# bigSevenV3.net
KiCad netlist of a schematic drawn in EAGLE
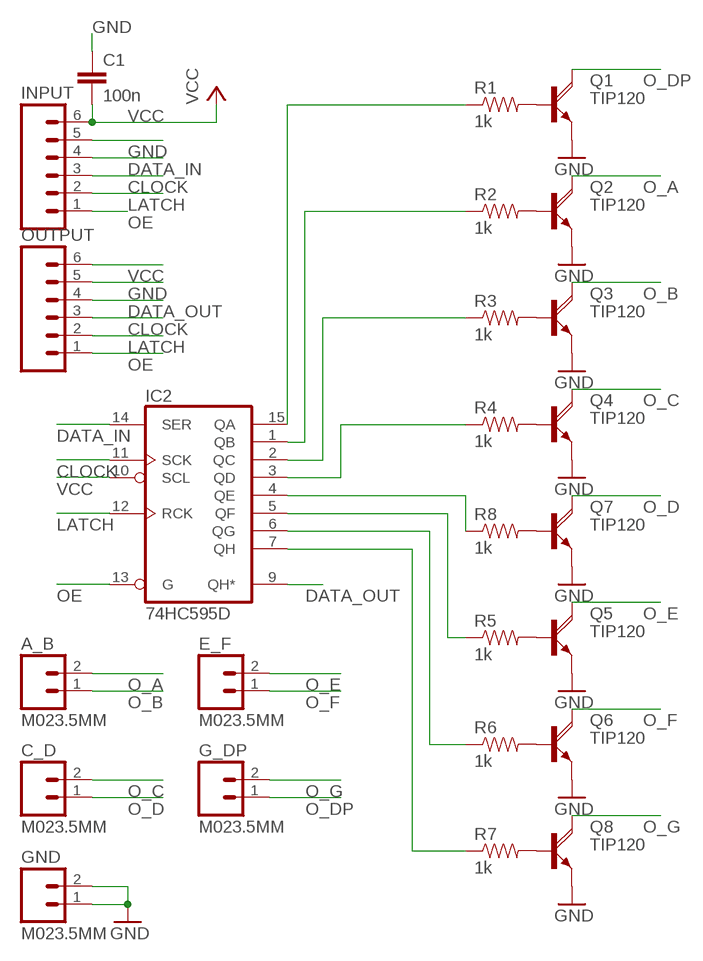
[diagram p0: schematic, sheet 1]

(export (version "E")
  (design (tool "Eeschema 10.0.6"))
  (components
    (comp (ref "A_B")
      (value "M023.5MM")
      (footprint "eagle-import:SCREWTERMINAL-3.5MM-2")
      (libsource (lib "eagle-import") (part "M023.5MM"))
    )
    (comp (ref "C1")
      (value "100n")
      (footprint "eagle-import:0805")
      (libsource (lib "eagle-import") (part "CAP0805"))
    )
    (comp (ref "C_D")
      (value "M023.5MM")
      (footprint "eagle-import:SCREWTERMINAL-3.5MM-2")
      (libsource (lib "eagle-import") (part "M023.5MM"))
    )
    (comp (ref "E_F")
      (value "M023.5MM")
      (footprint "eagle-import:SCREWTERMINAL-3.5MM-2")
      (libsource (lib "eagle-import") (part "M023.5MM"))
    )
    (comp (ref "GND")
      (value "M023.5MM")
      (footprint "eagle-import:SCREWTERMINAL-3.5MM-2")
      (libsource (lib "eagle-import") (part "M023.5MM"))
    )
    (comp (ref "G_DP")
      (value "M023.5MM")
      (footprint "eagle-import:SCREWTERMINAL-3.5MM-2")
      (libsource (lib "eagle-import") (part "M023.5MM"))
    )
    (comp (ref "IC2")
      (value "74HC595D")
      (footprint "eagle-import:SO16")
      (libsource (lib "eagle-import") (part "74595DHC"))
    )
    (comp (ref "INPUT")
      (value "M06LOCK")
      (footprint "eagle-import:1X06_LOCK")
      (libsource (lib "eagle-import") (part "M06LOCK"))
    )
    (comp (ref "OUTPUT")
      (value "M06LOCK")
      (footprint "eagle-import:1X06_LOCK")
      (libsource (lib "eagle-import") (part "M06LOCK"))
    )
    (comp (ref "Q1")
      (value "TIP120")
      (footprint "eagle-import:TO220AH")
      (libsource (lib "eagle-import") (part "TIP120"))
    )
    (comp (ref "Q2")
      (value "TIP120")
      (footprint "eagle-import:TO220AH")
      (libsource (lib "eagle-import") (part "TIP120"))
    )
    (comp (ref "Q3")
      (value "TIP120")
      (footprint "eagle-import:TO220AH")
      (libsource (lib "eagle-import") (part "TIP120"))
    )
    (comp (ref "Q4")
      (value "TIP120")
      (footprint "eagle-import:TO220AH")
      (libsource (lib "eagle-import") (part "TIP120"))
    )
    (comp (ref "Q5")
      (value "TIP120")
      (footprint "eagle-import:TO220AH")
      (libsource (lib "eagle-import") (part "TIP120"))
    )
    (comp (ref "Q6")
      (value "TIP120")
      (footprint "eagle-import:TO220AH")
      (libsource (lib "eagle-import") (part "TIP120"))
    )
    (comp (ref "Q7")
      (value "TIP120")
      (footprint "eagle-import:TO220AH")
      (libsource (lib "eagle-import") (part "TIP120"))
    )
    (comp (ref "Q8")
      (value "TIP120")
      (footprint "eagle-import:TO220AH")
      (libsource (lib "eagle-import") (part "TIP120"))
    )
    (comp (ref "R1")
      (value "1k")
      (footprint "eagle-import:0805")
      (libsource (lib "eagle-import") (part "RESISTOR0805-RES"))
    )
    (comp (ref "R2")
      (value "1k")
      (footprint "eagle-import:0805")
      (libsource (lib "eagle-import") (part "RESISTOR0805-RES"))
    )
    (comp (ref "R3")
      (value "1k")
      (footprint "eagle-import:0805")
      (libsource (lib "eagle-import") (part "RESISTOR0805-RES"))
    )
    (comp (ref "R4")
      (value "1k")
      (footprint "eagle-import:0805")
      (libsource (lib "eagle-import") (part "RESISTOR0805-RES"))
    )
    (comp (ref "R5")
      (value "1k")
      (footprint "eagle-import:0805")
      (libsource (lib "eagle-import") (part "RESISTOR0805-RES"))
    )
    (comp (ref "R6")
      (value "1k")
      (footprint "eagle-import:0805")
      (libsource (lib "eagle-import") (part "RESISTOR0805-RES"))
    )
    (comp (ref "R7")
      (value "1k")
      (footprint "eagle-import:0805")
      (libsource (lib "eagle-import") (part "RESISTOR0805-RES"))
    )
    (comp (ref "R8")
      (value "1k")
      (footprint "eagle-import:0805")
      (libsource (lib "eagle-import") (part "RESISTOR0805-RES"))
    )
  )
  (nets
    (net (code "1") (name "/CLOCK") (class "Default")
      (node (ref "IC2") (pin "11") (pinfunction "SCK_11") (pintype "input"))
      (node (ref "INPUT") (pin "3") (pinfunction "3_3") (pintype "passive"))
      (node (ref "OUTPUT") (pin "3") (pinfunction "3_3") (pintype "passive"))
    )
    (net (code "2") (name "/DATA_IN") (class "Default")
      (node (ref "IC2") (pin "14") (pinfunction "SER_14") (pintype "input"))
      (node (ref "INPUT") (pin "4") (pinfunction "4_4") (pintype "passive"))
    )
    (net (code "3") (name "/DATA_OUT") (class "Default")
      (node (ref "IC2") (pin "9") (pinfunction "QH*_9") (pintype "tri_state"))
      (node (ref "OUTPUT") (pin "4") (pinfunction "4_4") (pintype "passive"))
    )
    (net (code "4") (name "/LATCH") (class "Default")
      (node (ref "IC2") (pin "12") (pinfunction "RCK_12") (pintype "input"))
      (node (ref "INPUT") (pin "2") (pinfunction "2_2") (pintype "passive"))
      (node (ref "OUTPUT") (pin "2") (pinfunction "2_2") (pintype "passive"))
    )
    (net (code "5") (name "/OE") (class "Default")
      (node (ref "IC2") (pin "13") (pinfunction "G_13") (pintype "input"))
      (node (ref "INPUT") (pin "1") (pinfunction "1_1") (pintype "passive"))
      (node (ref "OUTPUT") (pin "1") (pinfunction "1_1") (pintype "passive"))
    )
    (net (code "6") (name "/O_A") (class "Default")
      (node (ref "A_B") (pin "2") (pinfunction "2_2") (pintype "passive"))
      (node (ref "Q2") (pin "C") (pinfunction "C_C") (pintype "passive"))
    )
    (net (code "7") (name "/O_B") (class "Default")
      (node (ref "A_B") (pin "1") (pinfunction "1_1") (pintype "passive"))
      (node (ref "Q3") (pin "C") (pinfunction "C_C") (pintype "passive"))
    )
    (net (code "8") (name "/O_C") (class "Default")
      (node (ref "C_D") (pin "2") (pinfunction "2_2") (pintype "passive"))
      (node (ref "Q4") (pin "C") (pinfunction "C_C") (pintype "passive"))
    )
    (net (code "9") (name "/O_D") (class "Default")
      (node (ref "C_D") (pin "1") (pinfunction "1_1") (pintype "passive"))
      (node (ref "Q7") (pin "C") (pinfunction "C_C") (pintype "passive"))
    )
    (net (code "10") (name "/O_DP") (class "Default")
      (node (ref "G_DP") (pin "1") (pinfunction "1_1") (pintype "passive"))
      (node (ref "Q1") (pin "C") (pinfunction "C_C") (pintype "passive"))
    )
    (net (code "11") (name "/O_E") (class "Default")
      (node (ref "E_F") (pin "2") (pinfunction "2_2") (pintype "passive"))
      (node (ref "Q5") (pin "C") (pinfunction "C_C") (pintype "passive"))
    )
    (net (code "12") (name "/O_F") (class "Default")
      (node (ref "E_F") (pin "1") (pinfunction "1_1") (pintype "passive"))
      (node (ref "Q6") (pin "C") (pinfunction "C_C") (pintype "passive"))
    )
    (net (code "13") (name "/O_G") (class "Default")
      (node (ref "G_DP") (pin "2") (pinfunction "2_2") (pintype "passive"))
      (node (ref "Q8") (pin "C") (pinfunction "C_C") (pintype "passive"))
    )
    (net (code "14") (name "GND") (class "Default")
      (node (ref "C1") (pin "1") (pinfunction "1_1") (pintype "passive"))
      (node (ref "GND") (pin "1") (pinfunction "1_1") (pintype "passive"))
      (node (ref "GND") (pin "2") (pinfunction "2_2") (pintype "passive"))
      (node (ref "INPUT") (pin "5") (pinfunction "5_5") (pintype "passive"))
      (node (ref "OUTPUT") (pin "5") (pinfunction "5_5") (pintype "passive"))
      (node (ref "Q1") (pin "E") (pinfunction "E_E") (pintype "passive"))
      (node (ref "Q2") (pin "E") (pinfunction "E_E") (pintype "passive"))
      (node (ref "Q3") (pin "E") (pinfunction "E_E") (pintype "passive"))
      (node (ref "Q4") (pin "E") (pinfunction "E_E") (pintype "passive"))
      (node (ref "Q5") (pin "E") (pinfunction "E_E") (pintype "passive"))
      (node (ref "Q6") (pin "E") (pinfunction "E_E") (pintype "passive"))
      (node (ref "Q7") (pin "E") (pinfunction "E_E") (pintype "passive"))
      (node (ref "Q8") (pin "E") (pinfunction "E_E") (pintype "passive"))
    )
    (net (code "15") (name "Net-(IC2A-QA)") (class "Default")
      (node (ref "IC2") (pin "15") (pinfunction "QA_15") (pintype "tri_state"))
      (node (ref "R1") (pin "1") (pinfunction "1_1") (pintype "passive"))
    )
    (net (code "16") (name "Net-(IC2A-QB)") (class "Default")
      (node (ref "IC2") (pin "1") (pinfunction "QB_1") (pintype "tri_state"))
      (node (ref "R2") (pin "1") (pinfunction "1_1") (pintype "passive"))
    )
    (net (code "17") (name "Net-(IC2A-QC)") (class "Default")
      (node (ref "IC2") (pin "2") (pinfunction "QC_2") (pintype "tri_state"))
      (node (ref "R3") (pin "1") (pinfunction "1_1") (pintype "passive"))
    )
    (net (code "18") (name "Net-(IC2A-QD)") (class "Default")
      (node (ref "IC2") (pin "3") (pinfunction "QD_3") (pintype "tri_state"))
      (node (ref "R4") (pin "1") (pinfunction "1_1") (pintype "passive"))
    )
    (net (code "19") (name "Net-(IC2A-QE)") (class "Default")
      (node (ref "IC2") (pin "4") (pinfunction "QE_4") (pintype "tri_state"))
      (node (ref "R8") (pin "1") (pinfunction "1_1") (pintype "passive"))
    )
    (net (code "20") (name "Net-(IC2A-QF)") (class "Default")
      (node (ref "IC2") (pin "5") (pinfunction "QF_5") (pintype "tri_state"))
      (node (ref "R5") (pin "1") (pinfunction "1_1") (pintype "passive"))
    )
    (net (code "21") (name "Net-(IC2A-QG)") (class "Default")
      (node (ref "IC2") (pin "6") (pinfunction "QG_6") (pintype "tri_state"))
      (node (ref "R6") (pin "1") (pinfunction "1_1") (pintype "passive"))
    )
    (net (code "22") (name "Net-(IC2A-QH)") (class "Default")
      (node (ref "IC2") (pin "7") (pinfunction "QH_7") (pintype "tri_state"))
      (node (ref "R7") (pin "1") (pinfunction "1_1") (pintype "passive"))
    )
    (net (code "23") (name "Net-(Q1-PadB)") (class "Default")
      (node (ref "Q1") (pin "B") (pinfunction "B_B") (pintype "passive"))
      (node (ref "R1") (pin "2") (pinfunction "2_2") (pintype "passive"))
    )
    (net (code "24") (name "Net-(Q2-PadB)") (class "Default")
      (node (ref "Q2") (pin "B") (pinfunction "B_B") (pintype "passive"))
      (node (ref "R2") (pin "2") (pinfunction "2_2") (pintype "passive"))
    )
    (net (code "25") (name "Net-(Q3-PadB)") (class "Default")
      (node (ref "Q3") (pin "B") (pinfunction "B_B") (pintype "passive"))
      (node (ref "R3") (pin "2") (pinfunction "2_2") (pintype "passive"))
    )
    (net (code "26") (name "Net-(Q4-PadB)") (class "Default")
      (node (ref "Q4") (pin "B") (pinfunction "B_B") (pintype "passive"))
      (node (ref "R4") (pin "2") (pinfunction "2_2") (pintype "passive"))
    )
    (net (code "27") (name "Net-(Q5-PadB)") (class "Default")
      (node (ref "Q5") (pin "B") (pinfunction "B_B") (pintype "passive"))
      (node (ref "R5") (pin "2") (pinfunction "2_2") (pintype "passive"))
    )
    (net (code "28") (name "Net-(Q6-PadB)") (class "Default")
      (node (ref "Q6") (pin "B") (pinfunction "B_B") (pintype "passive"))
      (node (ref "R6") (pin "2") (pinfunction "2_2") (pintype "passive"))
    )
    (net (code "29") (name "Net-(Q7-PadB)") (class "Default")
      (node (ref "Q7") (pin "B") (pinfunction "B_B") (pintype "passive"))
      (node (ref "R8") (pin "2") (pinfunction "2_2") (pintype "passive"))
    )
    (net (code "30") (name "Net-(Q8-PadB)") (class "Default")
      (node (ref "Q8") (pin "B") (pinfunction "B_B") (pintype "passive"))
      (node (ref "R7") (pin "2") (pinfunction "2_2") (pintype "passive"))
    )
    (net (code "31") (name "VCC") (class "Default")
      (node (ref "C1") (pin "2") (pinfunction "2_2") (pintype "passive"))
      (node (ref "IC2") (pin "10") (pinfunction "SCL_10") (pintype "input"))
      (node (ref "INPUT") (pin "6") (pinfunction "6_6") (pintype "passive"))
      (node (ref "OUTPUT") (pin "6") (pinfunction "6_6") (pintype "passive"))
    )
  )
)
